# FE.net
KiCad netlist of a schematic drawn in Altium Designer
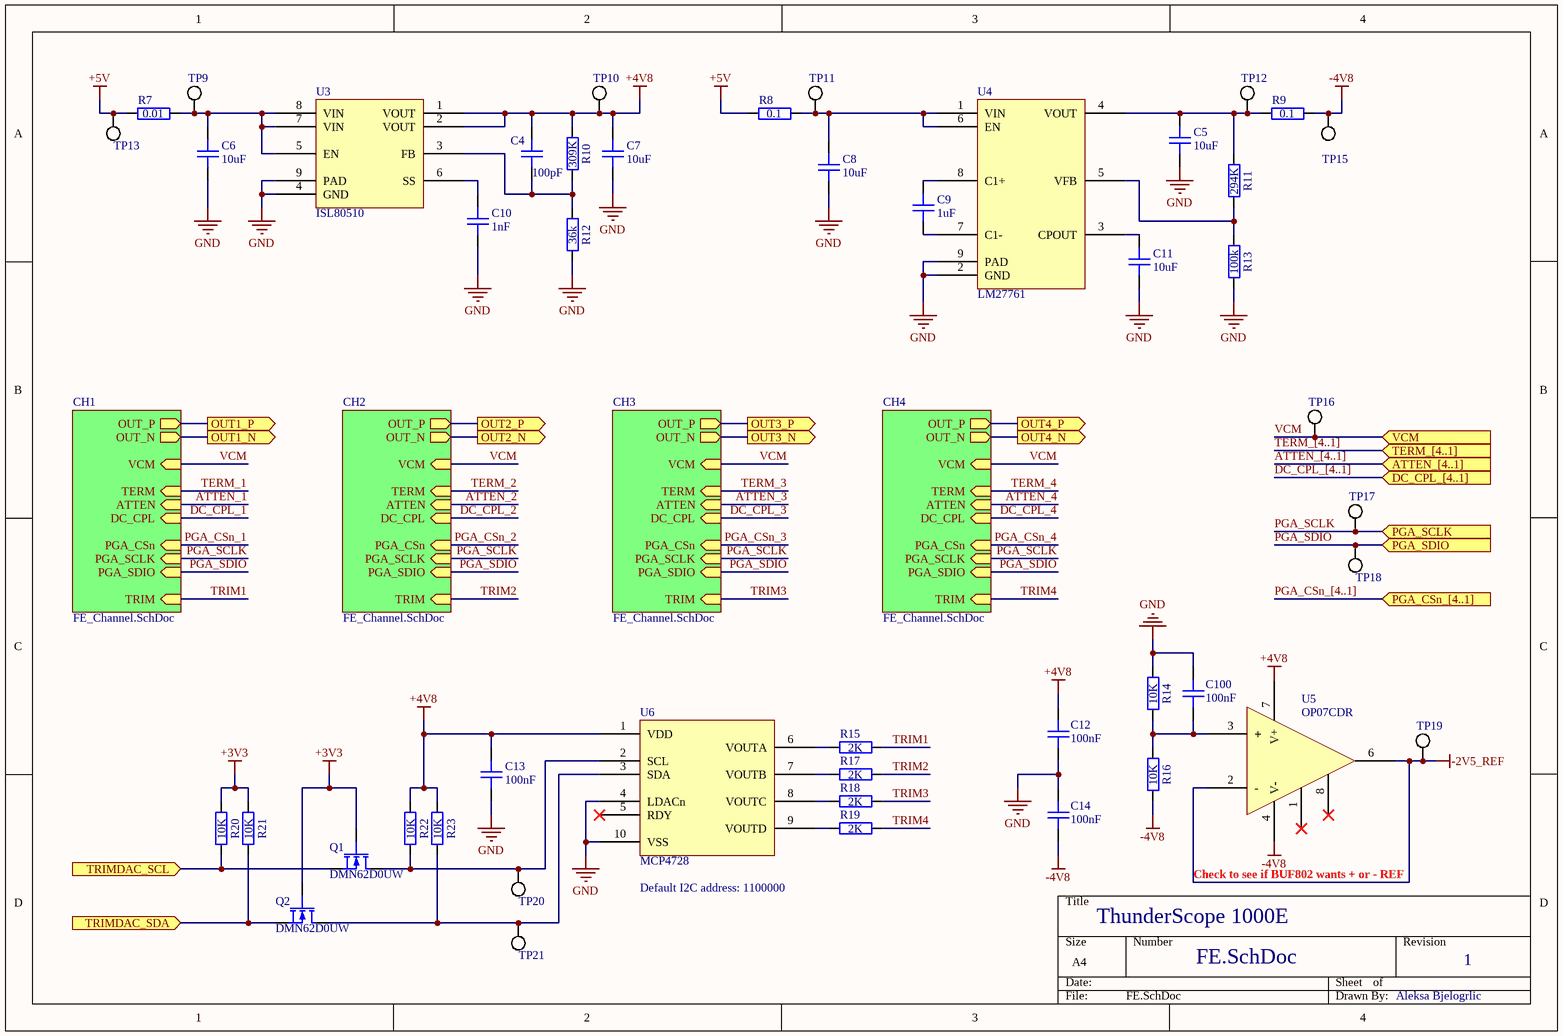
[diagram p0: FE.SchDoc]

(export (version "E")
  (design (tool "Eeschema 10.0.6"))
  (components
    (comp (ref "C4")
      (value "100pF")
      (footprint "GEN_C_0402")
      (libsource (lib "DSO") (part "CAP 100pF 50V C0G 0402"))
    )
    (comp (ref "C5")
      (value "10uF")
      (footprint "GEN_C_0603")
      (libsource (lib "DSO") (part "CAP 10uF 10V X5R 0603"))
    )
    (comp (ref "C6")
      (value "10uF")
      (footprint "GEN_C_0603")
      (libsource (lib "DSO") (part "CAP 10uF 10V X5R 0603"))
    )
    (comp (ref "C7")
      (value "10uF")
      (footprint "GEN_C_0603")
      (libsource (lib "DSO") (part "CAP 10uF 10V X5R 0603"))
    )
    (comp (ref "C8")
      (value "10uF")
      (footprint "GEN_C_0603")
      (libsource (lib "DSO") (part "CAP 10uF 10V X5R 0603"))
    )
    (comp (ref "C9")
      (value "1uF")
      (footprint "GEN_C_0402")
      (libsource (lib "DSO") (part "CAP 1uF 25V X5R 0402"))
    )
    (comp (ref "C10")
      (value "1nF")
      (footprint "GEN_C_0402")
      (libsource (lib "DSO") (part "CAP 1nF 50V C0G 0402"))
    )
    (comp (ref "C11")
      (value "10uF")
      (footprint "GEN_C_0603")
      (libsource (lib "DSO") (part "CAP 10uF 10V X5R 0603"))
    )
    (comp (ref "C12")
      (value "100nF")
      (footprint "GEN_C_0402")
      (libsource (lib "DSO") (part "CAP 100nF 16V X7R 0402"))
    )
    (comp (ref "C13")
      (value "100nF")
      (footprint "GEN_C_0402")
      (libsource (lib "DSO") (part "CAP 100nF 16V X7R 0402"))
    )
    (comp (ref "C14")
      (value "100nF")
      (footprint "GEN_C_0402")
      (libsource (lib "DSO") (part "CAP 100nF 16V X7R 0402"))
    )
    (comp (ref "C100")
      (value "100nF")
      (footprint "GEN_C_0402")
      (libsource (lib "DSO") (part "CAP 100nF 16V X7R 0402"))
    )
    (comp (ref "Q1")
      (value "DMN62D0UW")
      (footprint "GEN_SOT_323")
      (libsource (lib "DSO") (part "NMOS DMN62D0UW"))
    )
    (comp (ref "Q2")
      (value "DMN62D0UW")
      (footprint "GEN_SOT_323")
      (libsource (lib "DSO") (part "NMOS DMN62D0UW"))
    )
    (comp (ref "R7")
      (value "0.01")
      (footprint "GEN_R_0603")
      (fields (field (name "TOLERANCE") "1%"))
      (libsource (lib "DSO") (part "RES 0.01 OHM 1% 1/4W 0603"))
    )
    (comp (ref "R8")
      (value "0.1")
      (footprint "GEN_R_0402")
      (fields (field (name "TOLERANCE") "1%"))
      (libsource (lib "DSO") (part "RES 0.1 OHM 1% 1/6W 0402"))
    )
    (comp (ref "R9")
      (value "0.1")
      (footprint "GEN_R_0402")
      (fields (field (name "TOLERANCE") "1%"))
      (libsource (lib "DSO") (part "RES 0.1 OHM 1% 1/6W 0402"))
    )
    (comp (ref "R10")
      (value "309K")
      (footprint "GEN_R_0402")
      (fields (field (name "TOLERANCE") "1%"))
      (libsource (lib "DSO") (part "RES 309K OHM 1% 1/16W 0402"))
    )
    (comp (ref "R11")
      (value "294K")
      (footprint "GEN_R_0402")
      (fields (field (name "TOLERANCE") "1%"))
      (libsource (lib "DSO") (part "RES 294K OHM 1% 1/16W 0402"))
    )
    (comp (ref "R12")
      (value "36k")
      (footprint "GEN_R_0402")
      (fields (field (name "TOLERANCE") "1%"))
      (libsource (lib "DSO") (part "RES 36K OHM 1% 1/16W 0402"))
    )
    (comp (ref "R13")
      (value "100k")
      (footprint "GEN_R_0402")
      (fields (field (name "TOLERANCE") "1%"))
      (libsource (lib "DSO") (part "RES 100K OHM 1% 1/10W 0402"))
    )
    (comp (ref "R14")
      (value "10K")
      (footprint "GEN_R_0402")
      (fields (field (name "TOLERANCE") "1%"))
      (libsource (lib "DSO") (part "RES 10K OHM 1% 1/10W 0402"))
    )
    (comp (ref "R15")
      (value "2K")
      (footprint "GEN_R_0402")
      (fields (field (name "TOLERANCE") "1%"))
      (libsource (lib "DSO") (part "RES 2K OHM 1% 1/16W 0402"))
    )
    (comp (ref "R16")
      (value "10K")
      (footprint "GEN_R_0402")
      (fields (field (name "TOLERANCE") "1%"))
      (libsource (lib "DSO") (part "RES 10K OHM 1% 1/10W 0402"))
    )
    (comp (ref "R17")
      (value "2K")
      (footprint "GEN_R_0402")
      (fields (field (name "TOLERANCE") "1%"))
      (libsource (lib "DSO") (part "RES 2K OHM 1% 1/16W 0402"))
    )
    (comp (ref "R18")
      (value "2K")
      (footprint "GEN_R_0402")
      (fields (field (name "TOLERANCE") "1%"))
      (libsource (lib "DSO") (part "RES 2K OHM 1% 1/16W 0402"))
    )
    (comp (ref "R19")
      (value "2K")
      (footprint "GEN_R_0402")
      (fields (field (name "TOLERANCE") "1%"))
      (libsource (lib "DSO") (part "RES 2K OHM 1% 1/16W 0402"))
    )
    (comp (ref "R20")
      (value "10K")
      (footprint "GEN_R_0402")
      (fields (field (name "TOLERANCE") "1%"))
      (libsource (lib "") (part "RES 10K OHM 1% 1/10W 0402_1"))
    )
    (comp (ref "R21")
      (value "10K")
      (footprint "GEN_R_0402")
      (fields (field (name "TOLERANCE") "1%"))
      (libsource (lib "") (part "RES 10K OHM 1% 1/10W 0402_1"))
    )
    (comp (ref "R22")
      (value "10K")
      (footprint "GEN_R_0402")
      (fields (field (name "TOLERANCE") "1%"))
      (libsource (lib "") (part "RES 10K OHM 1% 1/10W 0402_1"))
    )
    (comp (ref "R23")
      (value "10K")
      (footprint "GEN_R_0402")
      (fields (field (name "TOLERANCE") "1%"))
      (libsource (lib "") (part "RES 10K OHM 1% 1/10W 0402_1"))
    )
    (comp (ref "TP9") (value "PCB") (footprint "GEN_TP_PCB") (libsource (lib "DSO") (part "TP PCB 1mm")))
    (comp (ref "TP10") (value "PCB") (footprint "GEN_TP_PCB") (libsource (lib "DSO") (part "TP PCB 1mm")))
    (comp (ref "TP11") (value "PCB") (footprint "GEN_TP_PCB") (libsource (lib "DSO") (part "TP PCB 1mm")))
    (comp (ref "TP12") (value "PCB") (footprint "GEN_TP_PCB") (libsource (lib "DSO") (part "TP PCB 1mm")))
    (comp (ref "TP13") (value "PCB") (footprint "GEN_TP_PCB") (libsource (lib "DSO") (part "TP PCB 1mm")))
    (comp (ref "TP15") (value "PCB") (footprint "GEN_TP_PCB") (libsource (lib "DSO") (part "TP PCB 1mm")))
    (comp (ref "TP16") (value "PCB") (footprint "GEN_TP_PCB") (libsource (lib "DSO") (part "TP PCB 1mm")))
    (comp (ref "TP17") (value "PCB") (footprint "GEN_TP_PCB") (libsource (lib "DSO") (part "TP PCB 1mm")))
    (comp (ref "TP18") (value "PCB") (footprint "GEN_TP_PCB") (libsource (lib "DSO") (part "TP PCB 1mm")))
    (comp (ref "TP19") (value "PCB") (footprint "GEN_TP_PCB") (libsource (lib "DSO") (part "TP PCB 1mm")))
    (comp (ref "TP20") (value "PCB") (footprint "GEN_TP_PCB") (libsource (lib "DSO") (part "TP PCB 1mm")))
    (comp (ref "TP21") (value "PCB") (footprint "GEN_TP_PCB") (libsource (lib "DSO") (part "TP PCB 1mm")))
    (comp (ref "U3")
      (value "ISL80510")
      (footprint "REN_DFN_ISL80510")
      (libsource (lib "DSO") (part "IC LDO ISL80510"))
    )
    (comp (ref "U4")
      (value "LM27761")
      (footprint "TI_WSON8_DSG0008A")
      (libsource (lib "DSO") (part "IC CPUMP LM27761"))
    )
    (comp (ref "U5")
      (value "OP07CDR")
      (footprint "TI_SOIC8_D0008A")
      (libsource (lib "DSO") (part "IC OPAMP OP07CDR"))
    )
    (comp (ref "U6")
      (value "MCP4728")
      (footprint "MC_MSOP10_UN")
      (libsource (lib "DSO") (part "IC DAC QUAD MCP4728"))
    )
  )
  (nets
    (net (code "1") (name "+3V3") (class "Default")
      (node (ref "Q1") (pin "2") (pinfunction "G_2") (pintype "passive"))
      (node (ref "Q2") (pin "2") (pinfunction "G_2") (pintype "passive"))
      (node (ref "R20") (pin "2") (pinfunction "2_2") (pintype "passive"))
      (node (ref "R21") (pin "2") (pinfunction "2_2") (pintype "passive"))
    )
    (net (code "2") (name "+4V8") (class "Default")
      (node (ref "C12") (pin "1") (pinfunction "1_1") (pintype "passive"))
      (node (ref "C13") (pin "2") (pinfunction "2_2") (pintype "passive"))
      (node (ref "C4") (pin "2") (pinfunction "2_2") (pintype "passive"))
      (node (ref "C7") (pin "2") (pinfunction "2_2") (pintype "passive"))
      (node (ref "R10") (pin "2") (pinfunction "2_2") (pintype "passive"))
      (node (ref "R22") (pin "2") (pinfunction "2_2") (pintype "passive"))
      (node (ref "R23") (pin "2") (pinfunction "2_2") (pintype "passive"))
      (node (ref "TP10") (pin "1") (pinfunction "1_1") (pintype "passive"))
      (node (ref "U3") (pin "1") (pinfunction "VOUT_1") (pintype "power_in"))
      (node (ref "U3") (pin "2") (pinfunction "VOUT_2") (pintype "power_in"))
      (node (ref "U5") (pin "7") (pinfunction "V+_7") (pintype "passive"))
      (node (ref "U6") (pin "1") (pinfunction "VDD_1") (pintype "power_in"))
    )
    (net (code "3") (name "+5V") (class "Default")
      (node (ref "R7") (pin "1") (pinfunction "1_1") (pintype "passive"))
      (node (ref "R8") (pin "1") (pinfunction "1_1") (pintype "passive"))
      (node (ref "TP13") (pin "1") (pinfunction "1_1") (pintype "passive"))
    )
    (net (code "4") (name "-2V5_REF") (class "Default")
      (node (ref "TP19") (pin "1") (pinfunction "1_1") (pintype "passive"))
      (node (ref "U5") (pin "2") (pinfunction "-_2") (pintype "passive"))
      (node (ref "U5") (pin "6") (pinfunction "OUT_6") (pintype "passive"))
    )
    (net (code "5") (name "-4V8") (class "Default")
      (node (ref "C14") (pin "2") (pinfunction "2_2") (pintype "passive"))
      (node (ref "R16") (pin "1") (pinfunction "1_1") (pintype "passive"))
      (node (ref "R9") (pin "2") (pinfunction "2_2") (pintype "passive"))
      (node (ref "TP15") (pin "1") (pinfunction "1_1") (pintype "passive"))
      (node (ref "U5") (pin "4") (pinfunction "V-_4") (pintype "passive"))
    )
    (net (code "29") (name "/PGA_SCLK") (class "Default")
      (node (ref "TP17") (pin "1") (pinfunction "1_1") (pintype "passive"))
    )
    (net (code "30") (name "/PGA_SDIO") (class "Default")
      (node (ref "TP18") (pin "1") (pinfunction "1_1") (pintype "passive"))
    )
    (net (code "36") (name "/TRIM1") (class "Default")
      (node (ref "R15") (pin "1") (pinfunction "1_1") (pintype "passive"))
    )
    (net (code "37") (name "/TRIM2") (class "Default")
      (node (ref "R17") (pin "1") (pinfunction "1_1") (pintype "passive"))
    )
    (net (code "38") (name "/TRIM3") (class "Default")
      (node (ref "R18") (pin "1") (pinfunction "1_1") (pintype "passive"))
    )
    (net (code "39") (name "/TRIM4") (class "Default")
      (node (ref "R19") (pin "1") (pinfunction "1_1") (pintype "passive"))
    )
    (net (code "40") (name "/TRIMDAC_SCL") (class "Default")
      (node (ref "Q1") (pin "3") (pinfunction "S_3") (pintype "passive"))
      (node (ref "R20") (pin "1") (pinfunction "1_1") (pintype "passive"))
    )
    (net (code "41") (name "/TRIMDAC_SDA") (class "Default")
      (node (ref "Q2") (pin "3") (pinfunction "S_3") (pintype "passive"))
      (node (ref "R21") (pin "1") (pinfunction "1_1") (pintype "passive"))
    )
    (net (code "42") (name "/VCM") (class "Default")
      (node (ref "TP16") (pin "1") (pinfunction "1_1") (pintype "passive"))
    )
    (net (code "43") (name "GND") (class "Default")
      (node (ref "C10") (pin "1") (pinfunction "1_1") (pintype "passive"))
      (node (ref "C100") (pin "1") (pinfunction "1_1") (pintype "passive"))
      (node (ref "C11") (pin "1") (pinfunction "1_1") (pintype "passive"))
      (node (ref "C12") (pin "2") (pinfunction "2_2") (pintype "passive"))
      (node (ref "C13") (pin "1") (pinfunction "1_1") (pintype "passive"))
      (node (ref "C14") (pin "1") (pinfunction "1_1") (pintype "passive"))
      (node (ref "C5") (pin "1") (pinfunction "1_1") (pintype "passive"))
      (node (ref "C6") (pin "1") (pinfunction "1_1") (pintype "passive"))
      (node (ref "C7") (pin "1") (pinfunction "1_1") (pintype "passive"))
      (node (ref "C8") (pin "1") (pinfunction "1_1") (pintype "passive"))
      (node (ref "R12") (pin "1") (pinfunction "1_1") (pintype "passive"))
      (node (ref "R13") (pin "1") (pinfunction "1_1") (pintype "passive"))
      (node (ref "R14") (pin "2") (pinfunction "2_2") (pintype "passive"))
      (node (ref "U3") (pin "4") (pinfunction "GND_4") (pintype "power_in"))
      (node (ref "U3") (pin "9") (pinfunction "PAD_9") (pintype "passive"))
      (node (ref "U4") (pin "2") (pinfunction "GND_2") (pintype "power_in"))
      (node (ref "U4") (pin "9") (pinfunction "PAD_9") (pintype "power_in"))
      (node (ref "U6") (pin "10") (pinfunction "VSS_10") (pintype "power_in"))
      (node (ref "U6") (pin "4") (pinfunction "LDACn_4") (pintype "passive"))
    )
    (net (code "44") (name "Net-(Q1-D)") (class "Default")
      (node (ref "Q1") (pin "1") (pinfunction "D_1") (pintype "passive"))
      (node (ref "R22") (pin "1") (pinfunction "1_1") (pintype "passive"))
      (node (ref "TP20") (pin "1") (pinfunction "1_1") (pintype "passive"))
      (node (ref "U6") (pin "2") (pinfunction "SCL_2") (pintype "passive"))
    )
    (net (code "45") (name "Net-(Q2-D)") (class "Default")
      (node (ref "Q2") (pin "1") (pinfunction "D_1") (pintype "passive"))
      (node (ref "R23") (pin "1") (pinfunction "1_1") (pintype "passive"))
      (node (ref "TP21") (pin "1") (pinfunction "1_1") (pintype "passive"))
      (node (ref "U6") (pin "3") (pinfunction "SDA_3") (pintype "passive"))
    )
    (net (code "46") (name "Net-(U3-EN)") (class "Default")
      (node (ref "C6") (pin "2") (pinfunction "2_2") (pintype "passive"))
      (node (ref "R7") (pin "2") (pinfunction "2_2") (pintype "passive"))
      (node (ref "TP9") (pin "1") (pinfunction "1_1") (pintype "passive"))
      (node (ref "U3") (pin "5") (pinfunction "EN_5") (pintype "passive"))
      (node (ref "U3") (pin "7") (pinfunction "VIN_7") (pintype "power_in"))
      (node (ref "U3") (pin "8") (pinfunction "VIN_8") (pintype "power_in"))
    )
    (net (code "47") (name "Net-(U3-FB)") (class "Default")
      (node (ref "C4") (pin "1") (pinfunction "1_1") (pintype "passive"))
      (node (ref "R10") (pin "1") (pinfunction "1_1") (pintype "passive"))
      (node (ref "R12") (pin "2") (pinfunction "2_2") (pintype "passive"))
      (node (ref "U3") (pin "3") (pinfunction "FB_3") (pintype "passive"))
    )
    (net (code "48") (name "Net-(U3-SS)") (class "Default")
      (node (ref "C10") (pin "2") (pinfunction "2_2") (pintype "passive"))
      (node (ref "U3") (pin "6") (pinfunction "SS_6") (pintype "passive"))
    )
    (net (code "49") (name "Net-(U4-C1+)") (class "Default")
      (node (ref "C9") (pin "2") (pinfunction "2_2") (pintype "passive"))
      (node (ref "U4") (pin "8") (pinfunction "C1+_8") (pintype "passive"))
    )
    (net (code "50") (name "Net-(U4-C1-)") (class "Default")
      (node (ref "C9") (pin "1") (pinfunction "1_1") (pintype "passive"))
      (node (ref "U4") (pin "7") (pinfunction "C1-_7") (pintype "passive"))
    )
    (net (code "51") (name "Net-(U4-CPOUT)") (class "Default")
      (node (ref "C11") (pin "2") (pinfunction "2_2") (pintype "passive"))
      (node (ref "U4") (pin "3") (pinfunction "CPOUT_3") (pintype "passive"))
    )
    (net (code "52") (name "Net-(U4-EN)") (class "Default")
      (node (ref "C8") (pin "2") (pinfunction "2_2") (pintype "passive"))
      (node (ref "R8") (pin "2") (pinfunction "2_2") (pintype "passive"))
      (node (ref "TP11") (pin "1") (pinfunction "1_1") (pintype "passive"))
      (node (ref "U4") (pin "1") (pinfunction "VIN_1") (pintype "power_in"))
      (node (ref "U4") (pin "6") (pinfunction "EN_6") (pintype "passive"))
    )
    (net (code "53") (name "Net-(U4-VFB)") (class "Default")
      (node (ref "R11") (pin "1") (pinfunction "1_1") (pintype "passive"))
      (node (ref "R13") (pin "2") (pinfunction "2_2") (pintype "passive"))
      (node (ref "U4") (pin "5") (pinfunction "VFB_5") (pintype "passive"))
    )
    (net (code "54") (name "Net-(U4-VOUT)") (class "Default")
      (node (ref "C5") (pin "2") (pinfunction "2_2") (pintype "passive"))
      (node (ref "R11") (pin "2") (pinfunction "2_2") (pintype "passive"))
      (node (ref "R9") (pin "1") (pinfunction "1_1") (pintype "passive"))
      (node (ref "TP12") (pin "1") (pinfunction "1_1") (pintype "passive"))
      (node (ref "U4") (pin "4") (pinfunction "VOUT_4") (pintype "power_in"))
    )
    (net (code "55") (name "Net-(U5-+)") (class "Default")
      (node (ref "C100") (pin "2") (pinfunction "2_2") (pintype "passive"))
      (node (ref "R14") (pin "1") (pinfunction "1_1") (pintype "passive"))
      (node (ref "R16") (pin "2") (pinfunction "2_2") (pintype "passive"))
      (node (ref "U5") (pin "3") (pinfunction "+_3") (pintype "passive"))
    )
    (net (code "56") (name "Net-(U6-VOUTA)") (class "Default")
      (node (ref "R15") (pin "2") (pinfunction "2_2") (pintype "passive"))
      (node (ref "U6") (pin "6") (pinfunction "VOUTA_6") (pintype "passive"))
    )
    (net (code "57") (name "Net-(U6-VOUTB)") (class "Default")
      (node (ref "R17") (pin "2") (pinfunction "2_2") (pintype "passive"))
      (node (ref "U6") (pin "7") (pinfunction "VOUTB_7") (pintype "passive"))
    )
    (net (code "58") (name "Net-(U6-VOUTC)") (class "Default")
      (node (ref "R18") (pin "2") (pinfunction "2_2") (pintype "passive"))
      (node (ref "U6") (pin "8") (pinfunction "VOUTC_8") (pintype "passive"))
    )
    (net (code "59") (name "Net-(U6-VOUTD)") (class "Default")
      (node (ref "R19") (pin "2") (pinfunction "2_2") (pintype "passive"))
      (node (ref "U6") (pin "9") (pinfunction "VOUTD_9") (pintype "passive"))
    )
    (net (code "60") (name "unconnected-(U5-N1-Pad1)") (class "Default")
      (node (ref "U5") (pin "1") (pinfunction "N1_1") (pintype "passive+no_connect"))
    )
    (net (code "61") (name "unconnected-(U5-N2-Pad8)") (class "Default")
      (node (ref "U5") (pin "8") (pinfunction "N2_8") (pintype "passive+no_connect"))
    )
    (net (code "62") (name "unconnected-(U6-RDY-Pad5)") (class "Default")
      (node (ref "U6") (pin "5") (pinfunction "RDY_5") (pintype "passive+no_connect"))
    )
  )
)
